# Vsense_0-223_3V.net
KiCad netlist of a schematic drawn in Altium Designer
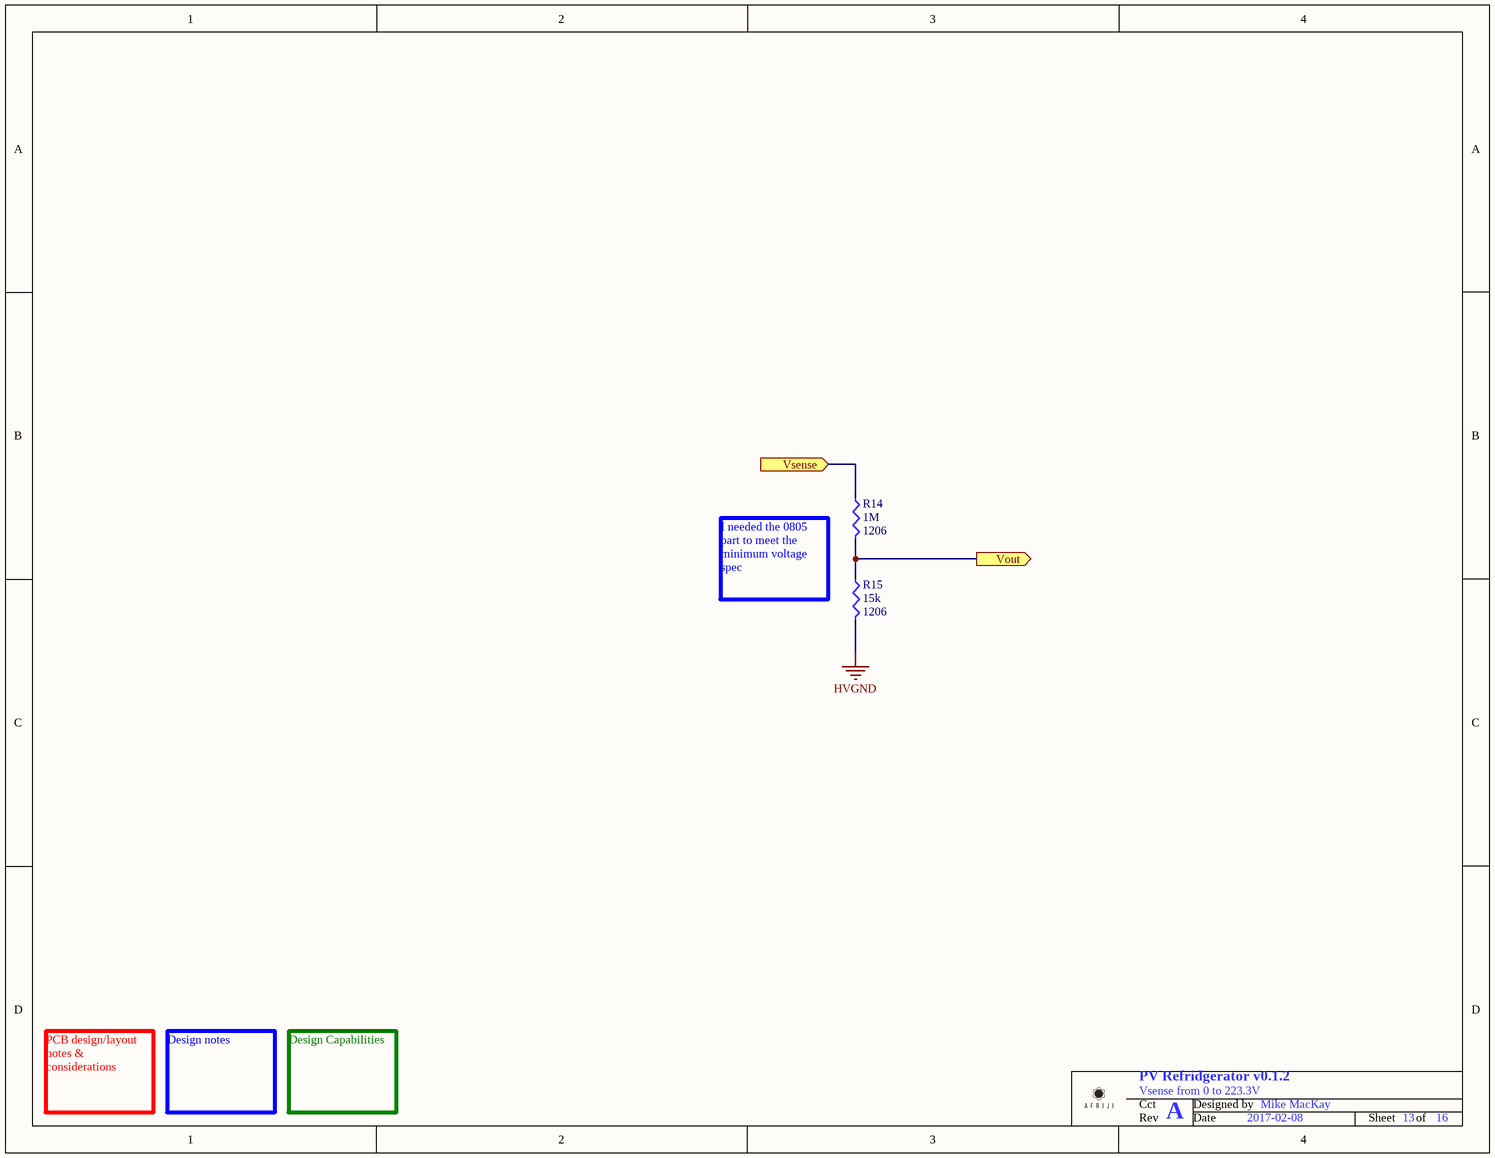
[diagram p0: Vsense 0-223.3V.SchDoc]

(export (version "E")
  (design (tool "Eeschema 10.0.6"))
  (components
    (comp (ref "R14")
      (value "Template - Resistor")
      (footprint "R1210")
      (description "Resistor")
      (fields
        (field (name "MANUFACTURER") "Yageo")
        (field (name "MANUFACTURER PART NUMBER") "RV1206FR-071ML")
        (field (name "RESISTANCE (OHMS)") "1M")
        (field (name "SUPPLIER DEVICE PACKAGE") "1206")
      )
      (libsource (lib "Integrated Component Library") (part "Template - Resistor"))
    )
    (comp (ref "R15")
      (value "Template - Resistor")
      (footprint "R1210")
      (description "RES SMD 15K OHM 1% 1/4W 1206")
      (fields
        (field (name "MANUFACTURER") "Yageo")
        (field (name "MANUFACTURER PART NUMBER") "RC1206FR-0715KL")
        (field (name "RESISTANCE (OHMS)") "15k")
        (field (name "SUPPLIER DEVICE PACKAGE") "1206")
      )
      (libsource (lib "Personal Library") (part "Template - Resistor"))
    )
  )
  (nets
    (net (code "1") (name "/Vout") (class "Default")
      (node (ref "R14") (pin "1") (pinfunction "1_1") (pintype "passive"))
      (node (ref "R15") (pin "2") (pinfunction "2_2") (pintype "passive"))
    )
    (net (code "2") (name "/Vsense") (class "Default")
      (node (ref "R14") (pin "2") (pinfunction "2_2") (pintype "passive"))
    )
    (net (code "3") (name "HVGND") (class "Default")
      (node (ref "R15") (pin "1") (pinfunction "1_1") (pintype "passive"))
    )
  )
)
